# ps_3PS.net
KiCad netlist of a schematic drawn in EAGLE
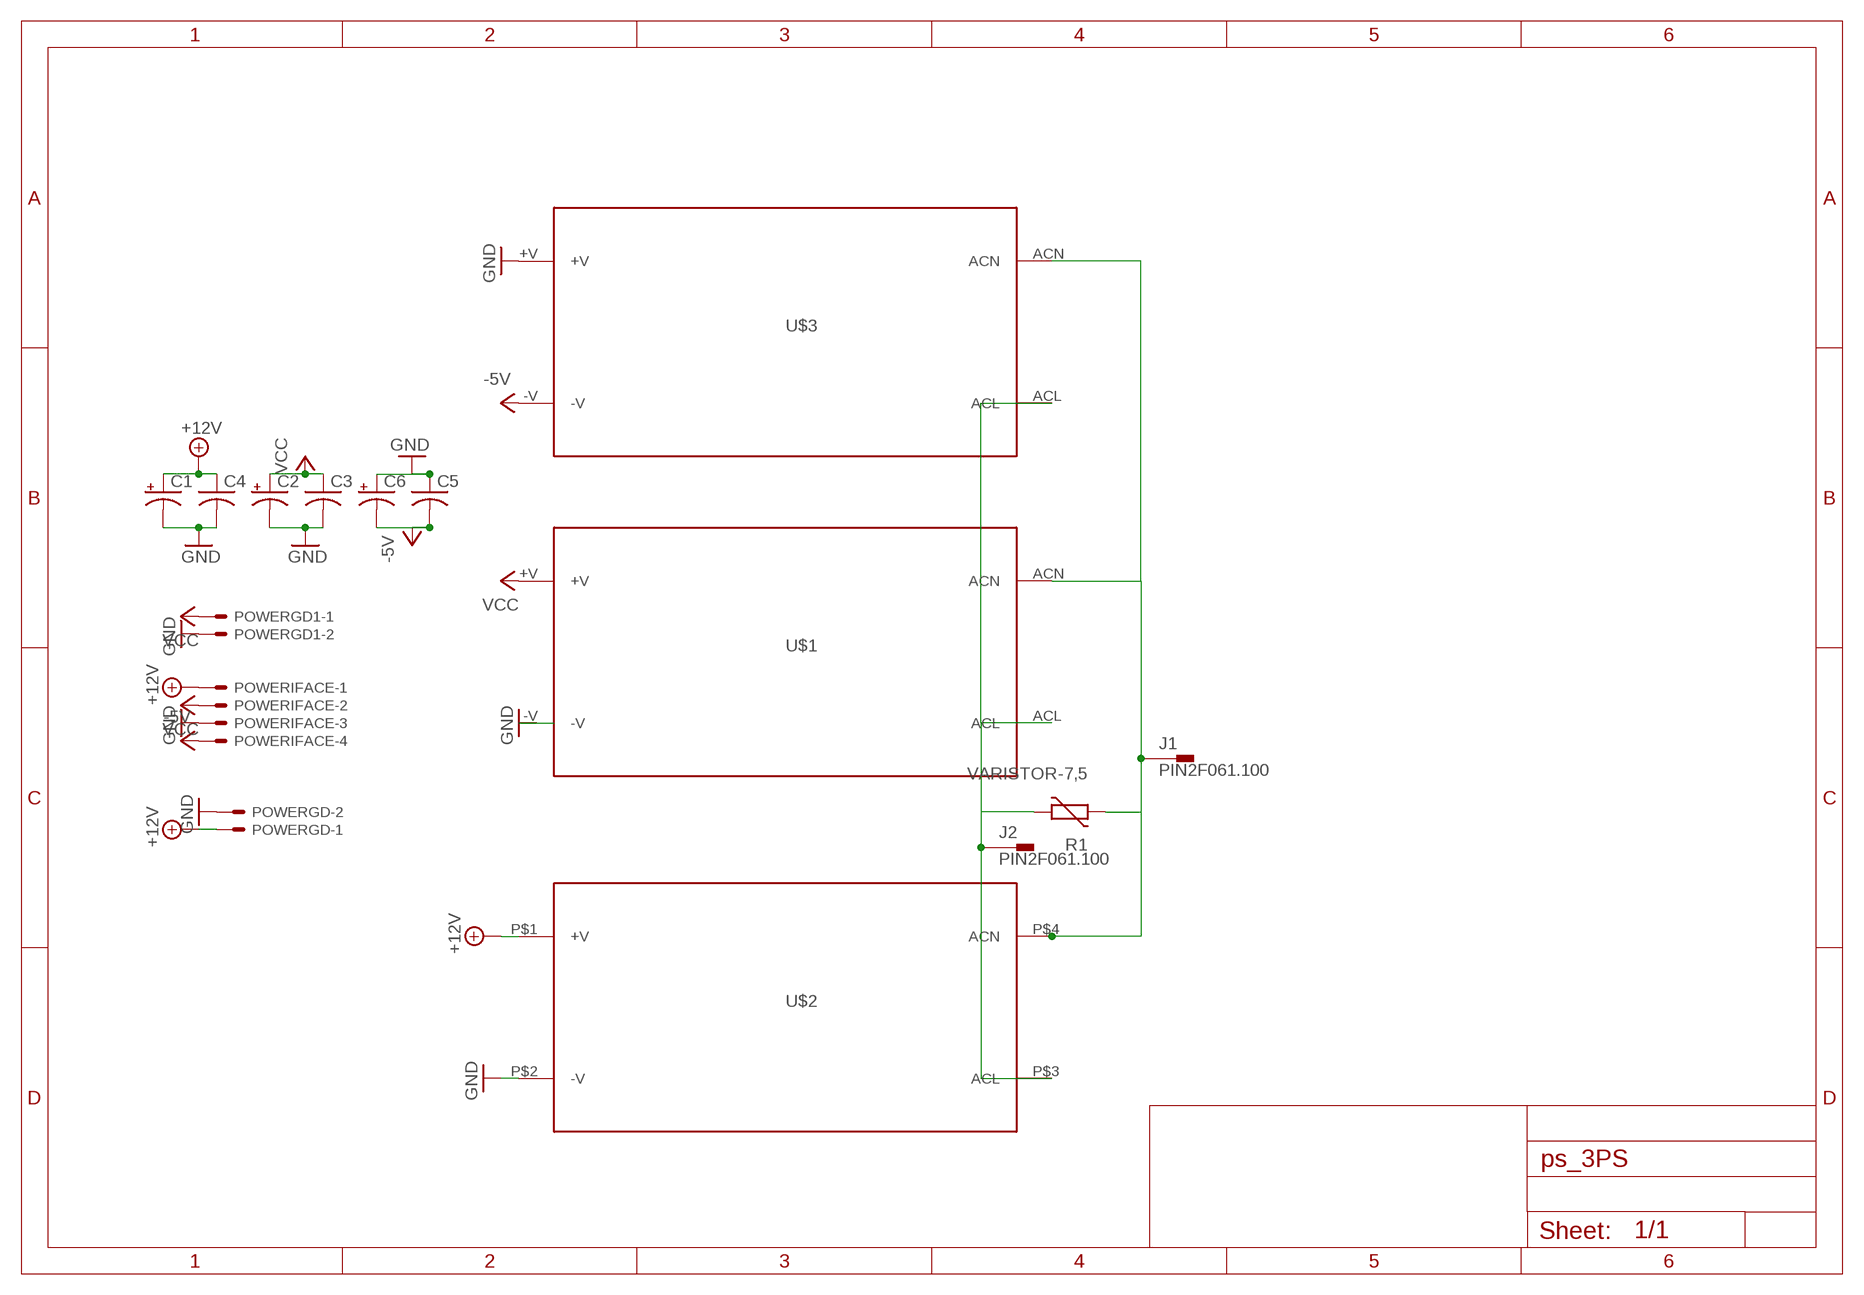
[diagram p0: schematic, sheet 1]

(export (version "E")
  (design (tool "Eeschema 10.0.6"))
  (components
    (comp (ref "C1")
      (value "CPOL-USE5-13")
      (footprint "eagle-import:E5-13")
      (libsource (lib "eagle-import") (part "CPOL-USE5-13"))
    )
    (comp (ref "C2")
      (value "CPOL-USE5-13")
      (footprint "eagle-import:E5-13")
      (libsource (lib "eagle-import") (part "CPOL-USE5-13"))
    )
    (comp (ref "C3")
      (value "C-US050-050X075")
      (footprint "eagle-import:C050-050X075")
      (libsource (lib "eagle-import") (part "C-US050-050X075"))
    )
    (comp (ref "C4")
      (value "C-US050-050X075")
      (footprint "eagle-import:C050-050X075")
      (libsource (lib "eagle-import") (part "C-US050-050X075"))
    )
    (comp (ref "C5")
      (value "C-US050-050X075")
      (footprint "eagle-import:C050-050X075")
      (libsource (lib "eagle-import") (part "C-US050-050X075"))
    )
    (comp (ref "C6")
      (value "CPOL-USE5-13")
      (footprint "eagle-import:E5-13")
      (libsource (lib "eagle-import") (part "CPOL-USE5-13"))
    )
    (comp (ref "J1")
      (value "PIN2F061.100")
      (footprint "eagle-import:F061.100")
      (libsource (lib "eagle-import") (part "PIN2F061.100"))
    )
    (comp (ref "J2")
      (value "PIN2F061.100")
      (footprint "eagle-import:F061.100")
      (libsource (lib "eagle-import") (part "PIN2F061.100"))
    )
    (comp (ref "POWERGD")
      (value "KK-156-2")
      (footprint "eagle-import:KK-156-2")
      (libsource (lib "eagle-import") (part "KK-156-2"))
    )
    (comp (ref "POWERGD1")
      (value "KK-156-2")
      (footprint "eagle-import:KK-156-2")
      (libsource (lib "eagle-import") (part "KK-156-2"))
    )
    (comp (ref "POWERIFACE")
      (value "KK-156-4")
      (footprint "eagle-import:KK-156-4")
      (libsource (lib "eagle-import") (part "KK-156-4"))
    )
    (comp (ref "R1")
      (value "VARISTOR-7,5")
      (footprint "eagle-import:R-7,5")
      (libsource (lib "eagle-import") (part "VARISTOR-7,5"))
    )
    (comp (ref "U$1")
      (value "IRM-05-05")
      (footprint "eagle-import:IRM-05-05")
      (libsource (lib "eagle-import") (part "IRM-05-05"))
    )
    (comp (ref "U$2")
      (value "IRM-60-12")
      (footprint "eagle-import:IRM-60-12")
      (libsource (lib "eagle-import") (part "IRM-60-12"))
    )
    (comp (ref "U$3")
      (value "IRM-05-05")
      (footprint "eagle-import:IRM-05-05")
      (libsource (lib "eagle-import") (part "IRM-05-05"))
    )
  )
  (nets
    (net (code "1") (name "+12V") (class "Default")
      (node (ref "C1") (pin "+") (pinfunction "+_+") (pintype "passive"))
      (node (ref "C4") (pin "1") (pinfunction "1_1") (pintype "passive"))
      (node (ref "POWERGD") (pin "1") (pinfunction "S_1") (pintype "passive"))
      (node (ref "POWERIFACE") (pin "1") (pinfunction "S_1") (pintype "passive"))
      (node (ref "U$2") (pin "P$1") (pinfunction "+V_P$1") (pintype "bidirectional"))
    )
    (net (code "2") (name "-5V") (class "Default")
      (node (ref "C5") (pin "2") (pinfunction "2_2") (pintype "passive"))
      (node (ref "C6") (pin "-") (pinfunction "-_-") (pintype "passive"))
      (node (ref "POWERIFACE") (pin "4") (pinfunction "S_4") (pintype "passive"))
      (node (ref "U$3") (pin "-V") (pinfunction "-V_-V") (pintype "bidirectional"))
    )
    (net (code "3") (name "GND") (class "Default")
      (node (ref "C1") (pin "-") (pinfunction "-_-") (pintype "passive"))
      (node (ref "C2") (pin "-") (pinfunction "-_-") (pintype "passive"))
      (node (ref "C3") (pin "2") (pinfunction "2_2") (pintype "passive"))
      (node (ref "C4") (pin "2") (pinfunction "2_2") (pintype "passive"))
      (node (ref "C5") (pin "1") (pinfunction "1_1") (pintype "passive"))
      (node (ref "C6") (pin "+") (pinfunction "+_+") (pintype "passive"))
      (node (ref "POWERGD") (pin "2") (pinfunction "S_2") (pintype "passive"))
      (node (ref "POWERGD1") (pin "2") (pinfunction "S_2") (pintype "passive"))
      (node (ref "POWERIFACE") (pin "3") (pinfunction "S_3") (pintype "passive"))
      (node (ref "U$1") (pin "-V") (pinfunction "-V_-V") (pintype "bidirectional"))
      (node (ref "U$2") (pin "P$2") (pinfunction "-V_P$2") (pintype "bidirectional"))
      (node (ref "U$3") (pin "+V") (pinfunction "+V_+V") (pintype "bidirectional"))
    )
    (net (code "4") (name "Net-(U$2-ACL)") (class "Default")
      (node (ref "J2") (pin "A1") (pinfunction "1_A1") (pintype "passive"))
      (node (ref "J2") (pin "A2") (pinfunction "1_A2") (pintype "passive"))
      (node (ref "R1") (pin "1") (pinfunction "1_1") (pintype "passive"))
      (node (ref "U$1") (pin "ACL") (pinfunction "ACL_ACL") (pintype "bidirectional"))
      (node (ref "U$2") (pin "P$3") (pinfunction "ACL_P$3") (pintype "bidirectional"))
      (node (ref "U$3") (pin "ACL") (pinfunction "ACL_ACL") (pintype "bidirectional"))
    )
    (net (code "5") (name "Net-(U$2-ACN)") (class "Default")
      (node (ref "J1") (pin "A1") (pinfunction "1_A1") (pintype "passive"))
      (node (ref "J1") (pin "A2") (pinfunction "1_A2") (pintype "passive"))
      (node (ref "R1") (pin "2") (pinfunction "2_2") (pintype "passive"))
      (node (ref "U$1") (pin "ACN") (pinfunction "ACN_ACN") (pintype "bidirectional"))
      (node (ref "U$2") (pin "P$4") (pinfunction "ACN_P$4") (pintype "bidirectional"))
      (node (ref "U$3") (pin "ACN") (pinfunction "ACN_ACN") (pintype "bidirectional"))
    )
    (net (code "6") (name "VCC") (class "Default")
      (node (ref "C2") (pin "+") (pinfunction "+_+") (pintype "passive"))
      (node (ref "C3") (pin "1") (pinfunction "1_1") (pintype "passive"))
      (node (ref "POWERGD1") (pin "1") (pinfunction "S_1") (pintype "passive"))
      (node (ref "POWERIFACE") (pin "2") (pinfunction "S_2") (pintype "passive"))
      (node (ref "U$1") (pin "+V") (pinfunction "+V_+V") (pintype "bidirectional"))
    )
  )
)
